# SdCard.net
KiCad netlist of a schematic drawn in Altium Designer
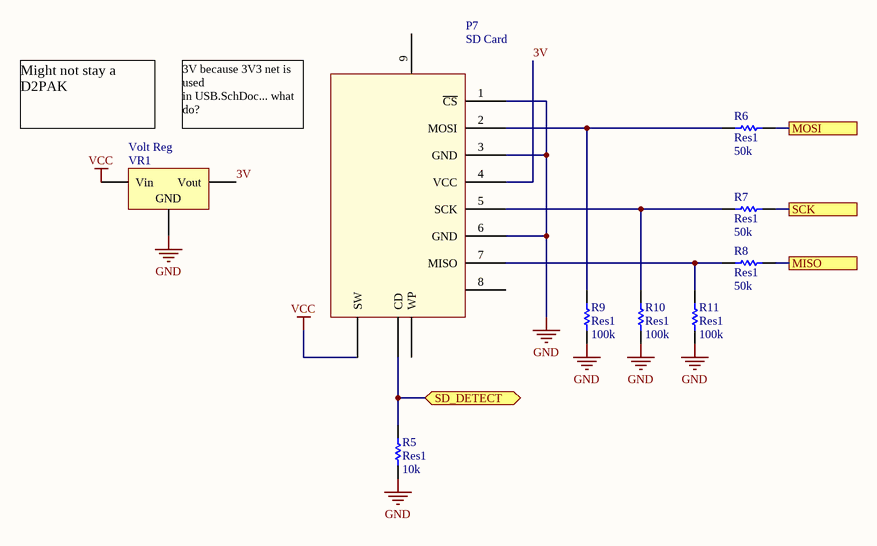
[diagram p0: SdCard.SchDoc]

(export (version "E")
  (design (tool "Eeschema 10.0.6"))
  (components
    (comp (ref "P7") (value "SD Card") (footprint "SD_CARD") (libsource (lib "SD_card") (part "SD Card")))
    (comp (ref "R5")
      (value "Res1")
      (footprint "6-0805_L")
      (description "Resistor")
      (fields (field (name "ALTIUM_VALUE") "10k") (field (name "PUBLISHER") "Altium Limited"))
      (libsource (lib "Miscellaneous Devices") (part "Res1"))
    )
    (comp (ref "R6")
      (value "Res1")
      (footprint "6-0805_N")
      (description "Resistor")
      (fields (field (name "ALTIUM_VALUE") "50k") (field (name "PUBLISHER") "Altium Limited"))
      (libsource (lib "Miscellaneous Devices") (part "Res1"))
    )
    (comp (ref "R7")
      (value "Res1")
      (footprint "6-0805_N")
      (description "Resistor")
      (fields (field (name "ALTIUM_VALUE") "50k") (field (name "PUBLISHER") "Altium Limited"))
      (libsource (lib "Miscellaneous Devices") (part "Res1"))
    )
    (comp (ref "R8")
      (value "Res1")
      (footprint "6-0805_N")
      (description "Resistor")
      (fields (field (name "ALTIUM_VALUE") "50k") (field (name "PUBLISHER") "Altium Limited"))
      (libsource (lib "Miscellaneous Devices") (part "Res1"))
    )
    (comp (ref "R9")
      (value "Res1")
      (footprint "6-0805_N")
      (description "Resistor")
      (fields (field (name "ALTIUM_VALUE") "100k") (field (name "PUBLISHER") "Altium Limited"))
      (libsource (lib "Miscellaneous Devices") (part "Res1"))
    )
    (comp (ref "R10")
      (value "Res1")
      (footprint "6-0805_N")
      (description "Resistor")
      (fields (field (name "ALTIUM_VALUE") "100k") (field (name "PUBLISHER") "Altium Limited"))
      (libsource (lib "Miscellaneous Devices") (part "Res1"))
    )
    (comp (ref "R11")
      (value "Res1")
      (footprint "6-0805_N")
      (description "Resistor")
      (fields (field (name "ALTIUM_VALUE") "100k") (field (name "PUBLISHER") "Altium Limited"))
      (libsource (lib "Miscellaneous Devices") (part "Res1"))
    )
    (comp (ref "VR1")
      (value "Volt Reg")
      (footprint "D2PAK_N")
      (description "Voltage Regulator")
      (fields (field (name "PUBLISHER") "Altium Limited"))
      (libsource (lib "Miscellaneous Devices") (part "Volt Reg"))
    )
  )
  (nets
    (net (code "1") (name "/3V") (class "Default")
      (node (ref "P7") (pin "4") (pinfunction "VCC_4") (pintype "passive"))
      (node (ref "VR1") (pin "3") (pinfunction "Vout_3") (pintype "passive"))
    )
    (net (code "2") (name "/MISO") (class "Default")
      (node (ref "R8") (pin "1") (pinfunction "1_1") (pintype "passive"))
    )
    (net (code "3") (name "/MOSI") (class "Default")
      (node (ref "R6") (pin "1") (pinfunction "1_1") (pintype "passive"))
    )
    (net (code "4") (name "/SCK") (class "Default")
      (node (ref "R7") (pin "1") (pinfunction "1_1") (pintype "passive"))
    )
    (net (code "5") (name "/SD_DETECT") (class "Default")
      (node (ref "P7") (pin "CD") (pinfunction "CD_CD") (pintype "passive"))
      (node (ref "R5") (pin "2") (pinfunction "2_2") (pintype "passive"))
    )
    (net (code "6") (name "GND") (class "Default")
      (node (ref "P7") (pin "1") (pinfunction "~{CS}_1") (pintype "passive"))
      (node (ref "P7") (pin "3") (pinfunction "GND_3") (pintype "passive"))
      (node (ref "P7") (pin "6") (pinfunction "GND_6") (pintype "passive"))
      (node (ref "R10") (pin "2") (pinfunction "2_2") (pintype "passive"))
      (node (ref "R11") (pin "2") (pinfunction "2_2") (pintype "passive"))
      (node (ref "R5") (pin "1") (pinfunction "1_1") (pintype "passive"))
      (node (ref "R9") (pin "2") (pinfunction "2_2") (pintype "passive"))
      (node (ref "VR1") (pin "2") (pinfunction "GND_2") (pintype "passive"))
    )
    (net (code "7") (name "Net-(P7-MISO)") (class "Default")
      (node (ref "P7") (pin "7") (pinfunction "MISO_7") (pintype "passive"))
      (node (ref "R11") (pin "1") (pinfunction "1_1") (pintype "passive"))
      (node (ref "R8") (pin "2") (pinfunction "2_2") (pintype "passive"))
    )
    (net (code "8") (name "Net-(P7-MOSI)") (class "Default")
      (node (ref "P7") (pin "2") (pinfunction "MOSI_2") (pintype "passive"))
      (node (ref "R6") (pin "2") (pinfunction "2_2") (pintype "passive"))
      (node (ref "R9") (pin "1") (pinfunction "1_1") (pintype "passive"))
    )
    (net (code "9") (name "Net-(P7-SCK)") (class "Default")
      (node (ref "P7") (pin "5") (pinfunction "SCK_5") (pintype "passive"))
      (node (ref "R10") (pin "1") (pinfunction "1_1") (pintype "passive"))
      (node (ref "R7") (pin "2") (pinfunction "2_2") (pintype "passive"))
    )
    (net (code "10") (name "VCC") (class "Default")
      (node (ref "P7") (pin "SW") (pinfunction "SW_SW") (pintype "passive"))
      (node (ref "VR1") (pin "1") (pinfunction "Vin_1") (pintype "passive"))
    )
    (net (code "11") (name "unconnected-(P7-Pad8)") (class "Default")
      (node (ref "P7") (pin "8") (pintype "passive"))
    )
    (net (code "12") (name "unconnected-(P7-Pad9)") (class "Default")
      (node (ref "P7") (pin "9") (pintype "passive"))
    )
    (net (code "13") (name "unconnected-(P7-PadWP)") (class "Default")
      (node (ref "P7") (pin "WP") (pinfunction "WP_WP") (pintype "passive"))
    )
  )
)
